# parent-board.net
KiCad netlist of a schematic drawn in EAGLE
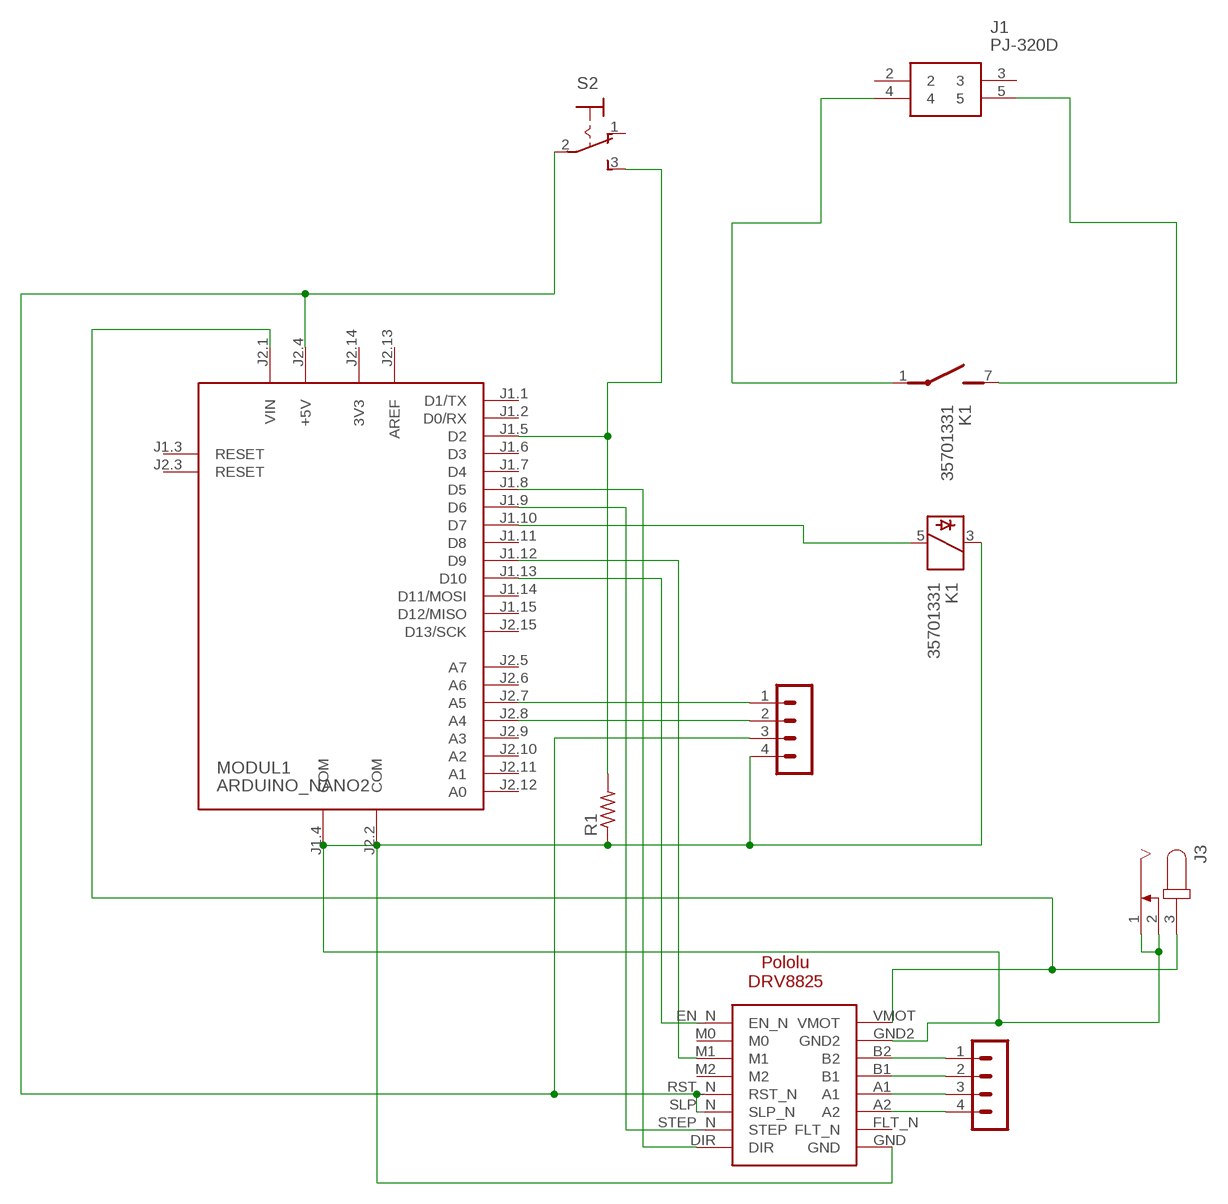
[diagram p0: schematic, sheet 1]

(export (version "E")
  (design (tool "Eeschema 10.0.6"))
  (components
    (comp (ref "J1")
      (value "PJ-320D")
      (footprint "eagle-import:PJ320D")
      (libsource (lib "eagle-import") (part "PJ-320D"))
    )
    (comp (ref "J2")
      (value "MA04-1")
      (footprint "eagle-import:MA04-1")
      (libsource (lib "eagle-import") (part "MA04-1"))
    )
    (comp (ref "J3")
      (value "JACK-PLUG0")
      (footprint "eagle-import:SPC4077")
      (libsource (lib "eagle-import") (part "JACK-PLUG0"))
    )
    (comp (ref "J4")
      (value "MA04-1")
      (footprint "eagle-import:MA04-1")
      (libsource (lib "eagle-import") (part "MA04-1"))
    )
    (comp (ref "K1")
      (value "35701331")
      (footprint "eagle-import:REED")
      (libsource (lib "eagle-import") (part "35701331"))
    )
    (comp (ref "MODUL1")
      (value "ARDUINO_NANO2")
      (footprint "eagle-import:ARDUINO_NANO2")
      (libsource (lib "eagle-import") (part "ARDUINO_NANO2"))
    )
    (comp (ref "R1")
      (value "R-US_M1206")
      (footprint "eagle-import:M1206")
      (libsource (lib "eagle-import") (part "R-US_M1206"))
    )
    (comp (ref "S2")
      (value "320-916")
      (footprint "eagle-import:320-916")
      (libsource (lib "eagle-import") (part "320-916"))
    )
    (comp (ref "U$1")
      (value "POLOLU-DRV8825")
      (footprint "eagle-import:POLOLU-DRV8825")
      (libsource (lib "eagle-import") (part "POLOLU-DRV8825"))
    )
  )
  (nets
    (net (code "1") (name "/3V3") (class "Default")
      (node (ref "MODUL1") (pin "J2.14") (pinfunction "3V3_J2.14") (pintype "power_in"))
    )
    (net (code "2") (name "/AREF") (class "Default")
      (node (ref "MODUL1") (pin "J2.13") (pinfunction "AREF_J2.13") (pintype "power_in"))
    )
    (net (code "3") (name "Net-(J2-Pad1)") (class "Default")
      (node (ref "J2") (pin "1") (pinfunction "1_1") (pintype "passive"))
      (node (ref "U$1") (pin "B2") (pinfunction "B2_B2") (pintype "bidirectional"))
    )
    (net (code "4") (name "Net-(J2-Pad2)") (class "Default")
      (node (ref "J2") (pin "2") (pinfunction "2_2") (pintype "passive"))
      (node (ref "U$1") (pin "B1") (pinfunction "B1_B1") (pintype "bidirectional"))
    )
    (net (code "5") (name "Net-(J2-Pad3)") (class "Default")
      (node (ref "J2") (pin "3") (pinfunction "3_3") (pintype "passive"))
      (node (ref "U$1") (pin "A1") (pinfunction "A1_A1") (pintype "bidirectional"))
    )
    (net (code "6") (name "Net-(J2-Pad4)") (class "Default")
      (node (ref "J2") (pin "4") (pinfunction "4_4") (pintype "passive"))
      (node (ref "U$1") (pin "A2") (pinfunction "A2_A2") (pintype "bidirectional"))
    )
    (net (code "7") (name "Net-(J3-Pad1)") (class "Default")
      (node (ref "J3") (pin "1") (pinfunction "1_1") (pintype "passive"))
      (node (ref "J3") (pin "2") (pinfunction "2_2") (pintype "passive"))
      (node (ref "J4") (pin "4") (pinfunction "4_4") (pintype "passive"))
      (node (ref "K1") (pin "3") (pinfunction "3_3") (pintype "passive"))
      (node (ref "MODUL1") (pin "J1.4") (pinfunction "COM_J1.4") (pintype "power_in"))
      (node (ref "MODUL1") (pin "J2.2") (pinfunction "COM_J2.2") (pintype "power_in"))
      (node (ref "R1") (pin "1") (pinfunction "1_1") (pintype "passive"))
      (node (ref "U$1") (pin "GND") (pinfunction "GND_GND") (pintype "bidirectional"))
      (node (ref "U$1") (pin "GND2") (pinfunction "GND2_GND2") (pintype "bidirectional"))
    )
    (net (code "8") (name "Net-(K1B-P)") (class "Default")
      (node (ref "J1") (pin "4") (pinfunction "4_4") (pintype "bidirectional"))
      (node (ref "K1") (pin "1") (pinfunction "P_1") (pintype "passive"))
    )
    (net (code "9") (name "Net-(K1B-S)") (class "Default")
      (node (ref "J1") (pin "5") (pinfunction "5_5") (pintype "bidirectional"))
      (node (ref "K1") (pin "7") (pinfunction "S_7") (pintype "passive"))
    )
    (net (code "10") (name "Net-(MODUL1-+5V)") (class "Default")
      (node (ref "J4") (pin "3") (pinfunction "3_3") (pintype "passive"))
      (node (ref "MODUL1") (pin "J2.4") (pinfunction "+5V_J2.4") (pintype "power_in"))
      (node (ref "S2") (pin "2") (pinfunction "P_2") (pintype "passive"))
      (node (ref "U$1") (pin "RST_N") (pinfunction "RST_N_RST_N") (pintype "bidirectional"))
      (node (ref "U$1") (pin "SLP_N") (pinfunction "SLP_N_SLP_N") (pintype "bidirectional"))
    )
    (net (code "11") (name "Net-(MODUL1-A4)") (class "Default")
      (node (ref "J4") (pin "2") (pinfunction "2_2") (pintype "passive"))
      (node (ref "MODUL1") (pin "J2.8") (pinfunction "A4_J2.8") (pintype "bidirectional"))
    )
    (net (code "12") (name "Net-(MODUL1-A5)") (class "Default")
      (node (ref "J4") (pin "1") (pinfunction "1_1") (pintype "passive"))
      (node (ref "MODUL1") (pin "J2.7") (pinfunction "A5_J2.7") (pintype "bidirectional"))
    )
    (net (code "13") (name "Net-(MODUL1-D2)") (class "Default")
      (node (ref "MODUL1") (pin "J1.5") (pinfunction "D2_J1.5") (pintype "bidirectional"))
      (node (ref "R1") (pin "2") (pinfunction "2_2") (pintype "passive"))
      (node (ref "S2") (pin "3") (pinfunction "S_3") (pintype "passive"))
    )
    (net (code "14") (name "Net-(MODUL1-D5)") (class "Default")
      (node (ref "MODUL1") (pin "J1.8") (pinfunction "D5_J1.8") (pintype "bidirectional"))
      (node (ref "U$1") (pin "DIR") (pinfunction "DIR_DIR") (pintype "bidirectional"))
    )
    (net (code "15") (name "Net-(MODUL1-D6)") (class "Default")
      (node (ref "MODUL1") (pin "J1.9") (pinfunction "D6_J1.9") (pintype "bidirectional"))
      (node (ref "U$1") (pin "STEP_N") (pinfunction "STEP_STEP_N") (pintype "bidirectional"))
    )
    (net (code "16") (name "Net-(MODUL1-D7)") (class "Default")
      (node (ref "K1") (pin "5") (pinfunction "5_5") (pintype "passive"))
      (node (ref "MODUL1") (pin "J1.10") (pinfunction "D7_J1.10") (pintype "bidirectional"))
    )
    (net (code "17") (name "Net-(MODUL1-D9)") (class "Default")
      (node (ref "MODUL1") (pin "J1.12") (pinfunction "D9_J1.12") (pintype "bidirectional"))
      (node (ref "U$1") (pin "M1") (pinfunction "M1_M1") (pintype "bidirectional"))
    )
    (net (code "18") (name "Net-(MODUL1-D10)") (class "Default")
      (node (ref "MODUL1") (pin "J1.13") (pinfunction "D10_J1.13") (pintype "bidirectional"))
      (node (ref "U$1") (pin "EN_N") (pinfunction "EN_N_EN_N") (pintype "bidirectional"))
    )
    (net (code "19") (name "Net-(MODUL1-VIN)") (class "Default")
      (node (ref "J3") (pin "3") (pinfunction "3_3") (pintype "passive"))
      (node (ref "MODUL1") (pin "J2.1") (pinfunction "VIN_J2.1") (pintype "power_in"))
      (node (ref "U$1") (pin "VMOT") (pinfunction "VMOT_VMOT") (pintype "bidirectional"))
    )
    (net (code "20") (name "unconnected-(J1-Pad2)") (class "Default")
      (node (ref "J1") (pin "2") (pinfunction "2_2") (pintype "bidirectional"))
    )
    (net (code "21") (name "unconnected-(J1-Pad3)") (class "Default")
      (node (ref "J1") (pin "3") (pinfunction "3_3") (pintype "bidirectional"))
    )
    (net (code "22") (name "unconnected-(MODUL1-A0-PadJ2.12)") (class "Default")
      (node (ref "MODUL1") (pin "J2.12") (pinfunction "A0_J2.12") (pintype "bidirectional"))
    )
    (net (code "23") (name "unconnected-(MODUL1-A1-PadJ2.11)") (class "Default")
      (node (ref "MODUL1") (pin "J2.11") (pinfunction "A1_J2.11") (pintype "bidirectional"))
    )
    (net (code "24") (name "unconnected-(MODUL1-A2-PadJ2.10)") (class "Default")
      (node (ref "MODUL1") (pin "J2.10") (pinfunction "A2_J2.10") (pintype "bidirectional"))
    )
    (net (code "25") (name "unconnected-(MODUL1-A3-PadJ2.9)") (class "Default")
      (node (ref "MODUL1") (pin "J2.9") (pinfunction "A3_J2.9") (pintype "bidirectional"))
    )
    (net (code "26") (name "unconnected-(MODUL1-A6-PadJ2.6)") (class "Default")
      (node (ref "MODUL1") (pin "J2.6") (pinfunction "A6_J2.6") (pintype "bidirectional"))
    )
    (net (code "27") (name "unconnected-(MODUL1-A7-PadJ2.5)") (class "Default")
      (node (ref "MODUL1") (pin "J2.5") (pinfunction "A7_J2.5") (pintype "bidirectional"))
    )
    (net (code "28") (name "unconnected-(MODUL1-D0{slash}RX-PadJ1.2)") (class "Default")
      (node (ref "MODUL1") (pin "J1.2") (pinfunction "D0/RX_J1.2") (pintype "bidirectional"))
    )
    (net (code "29") (name "unconnected-(MODUL1-D1{slash}TX-PadJ1.1)") (class "Default")
      (node (ref "MODUL1") (pin "J1.1") (pinfunction "D1/TX_J1.1") (pintype "bidirectional"))
    )
    (net (code "30") (name "unconnected-(MODUL1-D3-PadJ1.6)") (class "Default")
      (node (ref "MODUL1") (pin "J1.6") (pinfunction "D3_J1.6") (pintype "bidirectional"))
    )
    (net (code "31") (name "unconnected-(MODUL1-D4-PadJ1.7)") (class "Default")
      (node (ref "MODUL1") (pin "J1.7") (pinfunction "D4_J1.7") (pintype "bidirectional"))
    )
    (net (code "32") (name "unconnected-(MODUL1-D8-PadJ1.11)") (class "Default")
      (node (ref "MODUL1") (pin "J1.11") (pinfunction "D8_J1.11") (pintype "bidirectional"))
    )
    (net (code "33") (name "unconnected-(MODUL1-D11{slash}MOSI-PadJ1.14)") (class "Default")
      (node (ref "MODUL1") (pin "J1.14") (pinfunction "D11/MOSI_J1.14") (pintype "bidirectional"))
    )
    (net (code "34") (name "unconnected-(MODUL1-D12{slash}MISO-PadJ1.15)") (class "Default")
      (node (ref "MODUL1") (pin "J1.15") (pinfunction "D12/MISO_J1.15") (pintype "bidirectional"))
    )
    (net (code "35") (name "unconnected-(MODUL1-D13{slash}SCK-PadJ2.15)") (class "Default")
      (node (ref "MODUL1") (pin "J2.15") (pinfunction "D13/SCK_J2.15") (pintype "bidirectional"))
    )
    (net (code "36") (name "unconnected-(MODUL1-RESET-PadJ1.3)") (class "Default")
      (node (ref "MODUL1") (pin "J1.3") (pinfunction "RESET_J1.3") (pintype "bidirectional"))
    )
    (net (code "37") (name "unconnected-(MODUL1-RESET-PadJ2.3)") (class "Default")
      (node (ref "MODUL1") (pin "J2.3") (pinfunction "RESET_J2.3") (pintype "bidirectional"))
    )
    (net (code "38") (name "unconnected-(S2-O-Pad1)") (class "Default")
      (node (ref "S2") (pin "1") (pinfunction "O_1") (pintype "passive"))
    )
    (net (code "39") (name "unconnected-(U$1-PadFLT_N)") (class "Default")
      (node (ref "U$1") (pin "FLT_N") (pinfunction "FLT_N_FLT_N") (pintype "bidirectional"))
    )
    (net (code "40") (name "unconnected-(U$1-PadM0)") (class "Default")
      (node (ref "U$1") (pin "M0") (pinfunction "M0_M0") (pintype "bidirectional"))
    )
    (net (code "41") (name "unconnected-(U$1-PadM2)") (class "Default")
      (node (ref "U$1") (pin "M2") (pinfunction "M2_M2") (pintype "bidirectional"))
    )
  )
)
